# 2_PowerSupply.net
KiCad netlist of a schematic drawn in Altium Designer
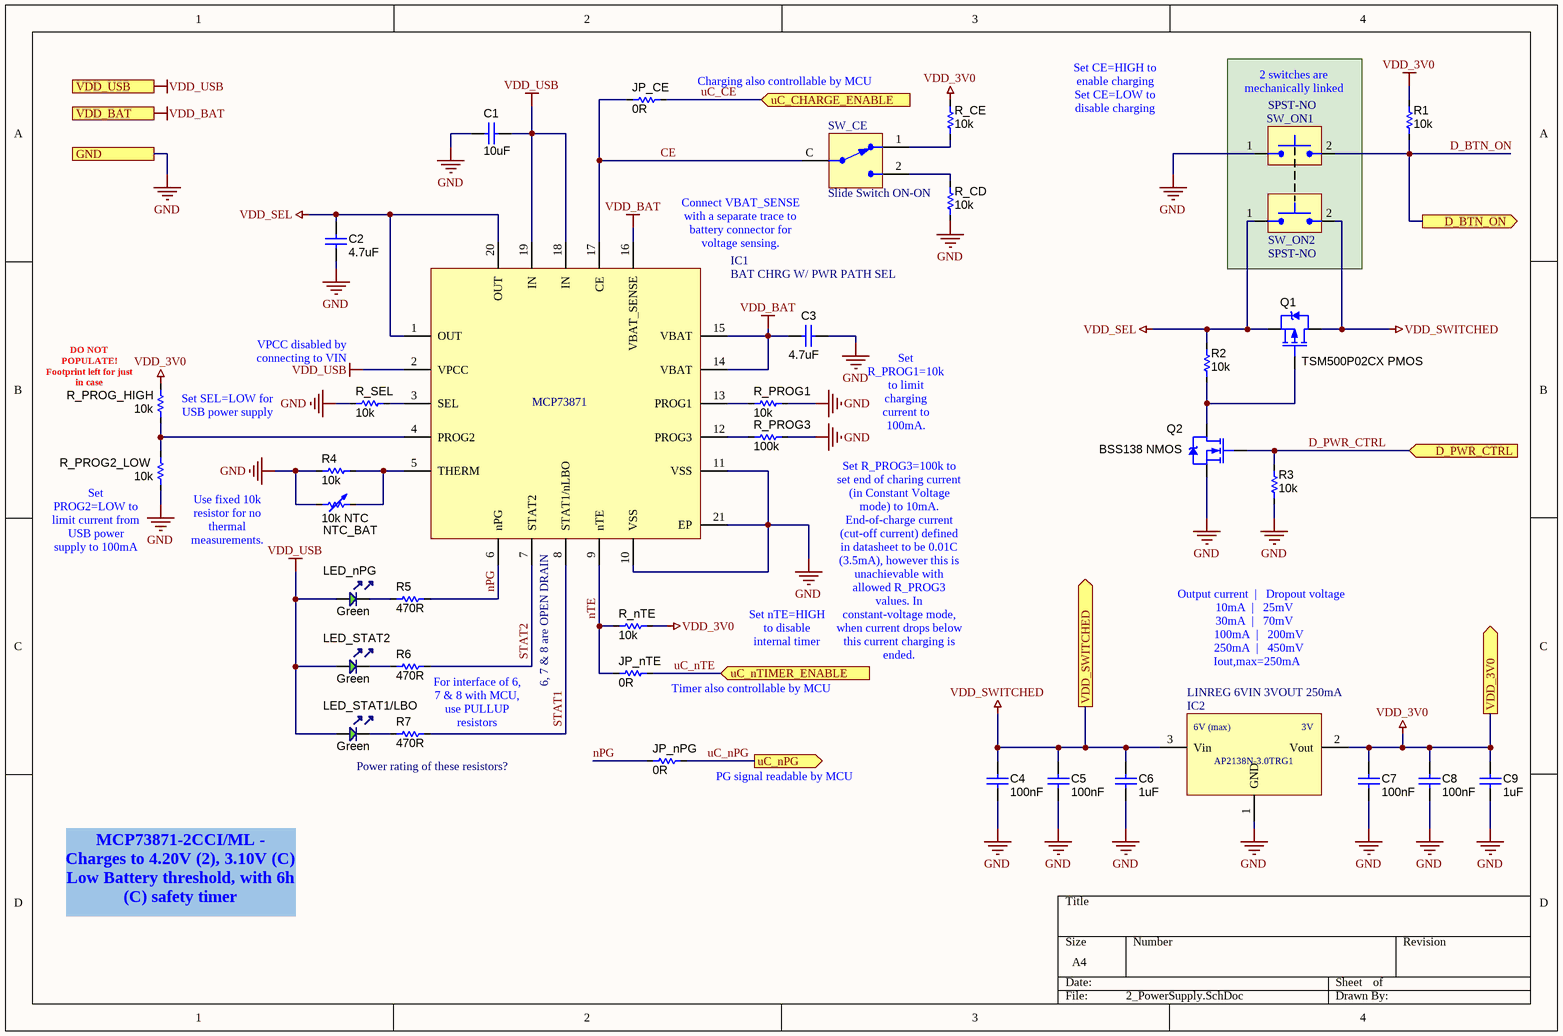
[diagram p0: 2_PowerSupply.SchDoc]

(export (version "E")
  (design (tool "Eeschema 10.0.6"))
  (components
    (comp (ref "C1")
      (value "10uF")
      (footprint "CAP_0603")
      (description "Cermacic Capacitor 0603 16V 10uF")
      (fields (field (name "MANUFACTURER") "n/a"))
      (libsource (lib "Diplomski") (part "CAP_10uF_16V_0603"))
    )
    (comp (ref "C2")
      (value "4.7uF")
      (footprint "CAP_0805")
      (description "Cermacic Capacitor 0805 25V 4.7uF")
      (fields (field (name "MANUFACTURER") "n/a"))
      (libsource (lib "Diplomski") (part "CAP_4.7uF_25V_0805"))
    )
    (comp (ref "C3")
      (value "4.7uF")
      (footprint "CAP_0805")
      (description "Cermacic Capacitor 0805 25V 4.7uF")
      (fields (field (name "MANUFACTURER") "n/a"))
      (libsource (lib "Diplomski") (part "CAP_4.7uF_25V_0805"))
    )
    (comp (ref "C4")
      (value "100nF")
      (footprint "CAP_0603")
      (description "Cermacic Capacitor 0603 50V 100nF")
      (fields (field (name "MANUFACTURER") "n/a"))
      (libsource (lib "Diplomski") (part "CAP_100nF_50V_0603"))
    )
    (comp (ref "C5")
      (value "100nF")
      (footprint "CAP_0603")
      (description "Cermacic Capacitor 0603 50V 100nF")
      (fields (field (name "MANUFACTURER") "n/a"))
      (libsource (lib "Diplomski") (part "CAP_100nF_50V_0603"))
    )
    (comp (ref "C6")
      (value "1uF")
      (footprint "CAP_0603")
      (description "Cermacic Capacitor 0603 16V 1uF")
      (fields (field (name "MANUFACTURER") "n/a"))
      (libsource (lib "Diplomski") (part "CAP_1uF_16V_0603"))
    )
    (comp (ref "C7")
      (value "100nF")
      (footprint "CAP_0603")
      (description "Cermacic Capacitor 0603 50V 100nF")
      (fields (field (name "MANUFACTURER") "n/a"))
      (libsource (lib "Diplomski") (part "CAP_100nF_50V_0603"))
    )
    (comp (ref "C8")
      (value "100nF")
      (footprint "CAP_0603")
      (description "Cermacic Capacitor 0603 50V 100nF")
      (fields (field (name "MANUFACTURER") "n/a"))
      (libsource (lib "Diplomski") (part "CAP_100nF_50V_0603"))
    )
    (comp (ref "C9")
      (value "1uF")
      (footprint "CAP_0603")
      (description "Cermacic Capacitor 0603 16V 1uF")
      (fields (field (name "MANUFACTURER") "n/a"))
      (libsource (lib "Diplomski") (part "CAP_1uF_16V_0603"))
    )
    (comp (ref "IC1")
      (value "BAT CHRG W/ PWR PATH SEL")
      (footprint "20-VFQFN EP (4mm x 4mm)")
      (fields
        (field (name "MANUFACTURER") "Microchip")
        (field (name "MANUFACTURER PART NUMBER") "MCP73871-2CCI/ML")
      )
      (libsource (lib "Diplomski") (part "IC_BATCHRG_PWRPATH_MCP73871"))
    )
    (comp (ref "IC2")
      (value "LINREG 6VIN 3VOUT 250mA")
      (footprint "SOT-23-3")
      (description "IC Linear Regulator Fixed 3V 250mA 6Vinmax SOT-23-3")
      (fields
        (field (name "MANUFACTURER") "Diodes Incorporated")
        (field (name "MANUFACTURER PART NUMBER") "AP2138N-3.0TRG1")
      )
      (libsource (lib "Diplomski") (part "IC_LINREG_6V_3V_250mA_SOT23-3"))
    )
    (comp (ref "JP_CE")
      (value "0R")
      (footprint "RES_0603")
      (description "Resistor SMD 0603 0R 0.1W 1%")
      (fields (field (name "MANUFACTURER") "n/a") (field (name "TOLERANCE") "1%"))
      (libsource (lib "Diplomski") (part "RES_0R_1%_0.1W_0603"))
    )
    (comp (ref "JP_nPG")
      (value "0R")
      (footprint "RES_0603")
      (description "Resistor SMD 0603 0R 0.1W 1%")
      (fields (field (name "MANUFACTURER") "n/a") (field (name "TOLERANCE") "1%"))
      (libsource (lib "Diplomski") (part "RES_0R_1%_0.1W_0603"))
    )
    (comp (ref "JP_nTE")
      (value "0R")
      (footprint "RES_0603")
      (description "Resistor SMD 0603 0R 0.1W 1%")
      (fields (field (name "MANUFACTURER") "n/a") (field (name "TOLERANCE") "1%"))
      (libsource (lib "Diplomski") (part "RES_0R_1%_0.1W_0603"))
    )
    (comp (ref "LED_nPG")
      (value "Green")
      (footprint "LED_0603")
      (description "LED Diode SMD Green")
      (fields (field (name "MANUFACTURER") "n/a"))
      (libsource (lib "Diplomski") (part "LED_Green_3V_20mA_0603"))
    )
    (comp (ref "LED_STAT1/LBO")
      (value "Green")
      (footprint "LED_0603")
      (description "LED Diode SMD Green")
      (fields (field (name "MANUFACTURER") "n/a"))
      (libsource (lib "Diplomski") (part "LED_Green_3V_20mA_0603"))
    )
    (comp (ref "LED_STAT2")
      (value "Green")
      (footprint "LED_0603")
      (description "LED Diode SMD Green")
      (fields (field (name "MANUFACTURER") "n/a"))
      (libsource (lib "Diplomski") (part "LED_Green_3V_20mA_0603"))
    )
    (comp (ref "NTC_BAT")
      (value "10k NTC")
      (footprint "RES VERT TH 5MM")
      (description "Thermistor NTC though-hole 10k @ 25degC 1/4W 10%")
      (fields (field (name "MANUFACTURER") "n/a") (field (name "TOLERANCE") "10%"))
      (libsource (lib "Diplomski") (part "THERM_NTC_10k_10%_0.25W_TH"))
    )
    (comp (ref "Q1")
      (value "TSM500P02CX PMOS")
      (footprint "SOT-23-3")
      (description "MOSFET P-channel SMD TSM500P02CX")
      (fields
        (field (name "MANUFACTURER") "Taiwan Semiconductor")
        (field (name "MANUFACTURER PART NUMBER") "TSM500P02CX")
      )
      (libsource (lib "Diplomski") (part "MOSFET_P_20V_4.7A_TSM500P02CX_SOT-23"))
    )
    (comp (ref "Q2")
      (value "BSS138 NMOS")
      (footprint "SOT-23-3")
      (description "MOSFET N-channel SMD BSS138 220mA 50V")
      (fields (field (name "MANUFACTURER") "ONsemi") (field (name "MANUFACTURER PART NUMBER") "BSS138"))
      (libsource (lib "Diplomski") (part "MOSFET_N_60V_220mA_BSS138_SOT-23"))
    )
    (comp (ref "R1")
      (value "10k")
      (footprint "RES_0603")
      (description "Resistor SMD 0603 10k 0.1W 1%")
      (fields (field (name "MANUFACTURER") "n/a") (field (name "TOLERANCE") "1%"))
      (libsource (lib "Diplomski") (part "RES_10k_1%_0.1W_0603"))
    )
    (comp (ref "R2")
      (value "10k")
      (footprint "RES_0603")
      (description "Resistor SMD 0603 10k 0.1W 1%")
      (fields (field (name "MANUFACTURER") "n/a") (field (name "TOLERANCE") "1%"))
      (libsource (lib "Diplomski") (part "RES_10k_1%_0.1W_0603"))
    )
    (comp (ref "R3")
      (value "10k")
      (footprint "RES_0603")
      (description "Resistor SMD 0603 10k 0.1W 1%")
      (fields (field (name "MANUFACTURER") "n/a") (field (name "TOLERANCE") "1%"))
      (libsource (lib "Diplomski") (part "RES_10k_1%_0.1W_0603"))
    )
    (comp (ref "R4")
      (value "10k")
      (footprint "RES_0603")
      (description "Resistor SMD 0603 10k 0.1W 1%")
      (fields (field (name "MANUFACTURER") "n/a") (field (name "TOLERANCE") "1%"))
      (libsource (lib "Diplomski") (part "RES_10k_1%_0.1W_0603"))
    )
    (comp (ref "R5")
      (value "470R")
      (footprint "RES_0603")
      (description "Resistor SMD 0603 0R 0.1W 1%")
      (fields (field (name "MANUFACTURER") "n/a") (field (name "TOLERANCE") "1%"))
      (libsource (lib "Diplomski") (part "RES_470R_1%_0.1W_0603"))
    )
    (comp (ref "R6")
      (value "470R")
      (footprint "RES_0603")
      (description "Resistor SMD 0603 0R 0.1W 1%")
      (fields (field (name "MANUFACTURER") "n/a") (field (name "TOLERANCE") "1%"))
      (libsource (lib "Diplomski") (part "RES_470R_1%_0.1W_0603"))
    )
    (comp (ref "R7")
      (value "470R")
      (footprint "RES_0603")
      (description "Resistor SMD 0603 0R 0.1W 1%")
      (fields (field (name "MANUFACTURER") "n/a") (field (name "TOLERANCE") "1%"))
      (libsource (lib "Diplomski") (part "RES_470R_1%_0.1W_0603"))
    )
    (comp (ref "R_CD")
      (value "10k")
      (footprint "RES_0603")
      (description "Resistor SMD 0603 10k 0.1W 1%")
      (fields (field (name "MANUFACTURER") "n/a") (field (name "TOLERANCE") "1%"))
      (libsource (lib "Diplomski") (part "RES_10k_1%_0.1W_0603"))
    )
    (comp (ref "R_CE")
      (value "10k")
      (footprint "RES_0603")
      (description "Resistor SMD 0603 10k 0.1W 1%")
      (fields (field (name "MANUFACTURER") "n/a") (field (name "TOLERANCE") "1%"))
      (libsource (lib "Diplomski") (part "RES_10k_1%_0.1W_0603"))
    )
    (comp (ref "R_nTE")
      (value "10k")
      (footprint "RES_0603")
      (description "Resistor SMD 0603 10k 0.1W 1%")
      (fields (field (name "MANUFACTURER") "n/a") (field (name "TOLERANCE") "1%"))
      (libsource (lib "Diplomski") (part "RES_10k_1%_0.1W_0603"))
    )
    (comp (ref "R_PROG1")
      (value "10k")
      (footprint "RES_0603")
      (description "Resistor SMD 0603 10k 0.1W 1%")
      (fields (field (name "MANUFACTURER") "n/a") (field (name "TOLERANCE") "1%"))
      (libsource (lib "Diplomski") (part "RES_10k_1%_0.1W_0603"))
    )
    (comp (ref "R_PROG2_LOW")
      (value "10k")
      (footprint "RES_0603")
      (description "Resistor SMD 0603 10k 0.1W 1%")
      (fields (field (name "MANUFACTURER") "n/a") (field (name "TOLERANCE") "1%"))
      (libsource (lib "Diplomski") (part "RES_10k_1%_0.1W_0603"))
    )
    (comp (ref "R_PROG3")
      (value "100k")
      (footprint "RES_0603")
      (description "Resistor SMD 0603 100k 0.1W 1%")
      (fields (field (name "MANUFACTURER") "n/a") (field (name "TOLERANCE") "1%"))
      (libsource (lib "Diplomski") (part "RES_100k_1%_0.1W_0603"))
    )
    (comp (ref "R_PROG_HIGH")
      (value "10k")
      (footprint "RES_0603")
      (description "Resistor SMD 0603 10k 0.1W 1%")
      (fields (field (name "MANUFACTURER") "n/a") (field (name "TOLERANCE") "1%"))
      (libsource (lib "Diplomski") (part "RES_10k_1%_0.1W_0603"))
    )
    (comp (ref "R_SEL")
      (value "10k")
      (footprint "RES_0603")
      (description "Resistor SMD 0603 10k 0.1W 1%")
      (fields (field (name "MANUFACTURER") "n/a") (field (name "TOLERANCE") "1%"))
      (libsource (lib "Diplomski") (part "RES_10k_1%_0.1W_0603"))
    )
    (comp (ref "SW_CE")
      (value "Slide Switch ON-ON")
      (footprint "SWITCH SPDT 2.54MM R/A")
      (description "Slide switch 2.54mm pitch Single Pole Double Throw (ON-ON) ESP201 Right Angle")
      (fields (field (name "MANUFACTURER") "ECE") (field (name "MANUFACTURER PART NUMBER") "ESP201"))
      (libsource (lib "Diplomski") (part "SWITCH_SLIDE_SPDT_ESP201_R/A_2.54mm"))
    )
    (comp (ref "SW_ON1")
      (value "SPST-NO")
      (footprint "SWITCH_TACTILE_SMD_6X3.5mm_2pin")
      (description "SMD Tactile switch 2 pin 6x3.5mm SPST-NO 5mm height")
      (fields (field (name "MANUFACTURER") "Diptronics") (field (name "MANUFACTURER PART NUMBER") "DTSM-32N"))
      (libsource (lib "Diplomski") (part "SWITCH_SMD_6X3.5mm_2pin"))
    )
    (comp (ref "SW_ON2")
      (value "SPST-NO")
      (footprint "SWITCH_TACTILE_SMD_6X3.5mm_2pin")
      (description "SMD Tactile switch 2 pin 6x3.5mm SPST-NO 5mm height")
      (fields (field (name "MANUFACTURER") "Diptronics") (field (name "MANUFACTURER PART NUMBER") "DTSM-32N"))
      (libsource (lib "Diplomski") (part "SWITCH_SMD_6X3.5mm_2pin"))
    )
  )
  (nets
    (net (code "1") (name "/CE") (class "Default")
      (node (ref "IC1") (pin "17") (pinfunction "CE_17") (pintype "passive"))
      (node (ref "JP_CE") (pin "1") (pinfunction "1_1") (pintype "passive"))
      (node (ref "SW_CE") (pin "C") (pinfunction "C_C") (pintype "passive"))
    )
    (net (code "2") (name "/D_BTN_ON") (class "Default")
      (node (ref "R1") (pin "1") (pinfunction "1_1") (pintype "passive"))
      (node (ref "SW_ON1") (pin "2") (pinfunction "2_2") (pintype "passive"))
    )
    (net (code "3") (name "/D_PWR_CTRL") (class "Default")
      (node (ref "Q2") (pin "1") (pinfunction "G_1") (pintype "passive"))
      (node (ref "R3") (pin "2") (pinfunction "2_2") (pintype "passive"))
    )
    (net (code "4") (name "/STAT1") (class "Default")
      (node (ref "IC1") (pin "8") (pinfunction "STAT1/nLBO_8") (pintype "passive"))
      (node (ref "R7") (pin "2") (pinfunction "2_2") (pintype "passive"))
    )
    (net (code "5") (name "/STAT2") (class "Default")
      (node (ref "IC1") (pin "7") (pinfunction "STAT2_7") (pintype "passive"))
      (node (ref "R6") (pin "2") (pinfunction "2_2") (pintype "passive"))
    )
    (net (code "6") (name "/nPG") (class "Default")
      (node (ref "IC1") (pin "6") (pinfunction "nPG_6") (pintype "passive"))
      (node (ref "JP_nPG") (pin "2") (pinfunction "2_2") (pintype "passive"))
      (node (ref "R5") (pin "2") (pinfunction "2_2") (pintype "passive"))
    )
    (net (code "7") (name "/nTE") (class "Default")
      (node (ref "IC1") (pin "9") (pinfunction "nTE_9") (pintype "passive"))
      (node (ref "JP_nTE") (pin "2") (pinfunction "2_2") (pintype "passive"))
      (node (ref "R_nTE") (pin "1") (pinfunction "1_1") (pintype "passive"))
    )
    (net (code "8") (name "/uC_CE") (class "Default")
      (node (ref "JP_CE") (pin "2") (pinfunction "2_2") (pintype "passive"))
    )
    (net (code "9") (name "/uC_nPG") (class "Default")
      (node (ref "JP_nPG") (pin "1") (pinfunction "1_1") (pintype "passive"))
    )
    (net (code "10") (name "/uC_nTE") (class "Default")
      (node (ref "JP_nTE") (pin "1") (pinfunction "1_1") (pintype "passive"))
    )
    (net (code "11") (name "GND") (class "Default")
      (node (ref "C1") (pin "2") (pinfunction "2_2") (pintype "passive"))
      (node (ref "C2") (pin "2") (pinfunction "2_2") (pintype "passive"))
      (node (ref "C3") (pin "2") (pinfunction "2_2") (pintype "passive"))
      (node (ref "C4") (pin "2") (pinfunction "2_2") (pintype "passive"))
      (node (ref "C5") (pin "2") (pinfunction "2_2") (pintype "passive"))
      (node (ref "C6") (pin "2") (pinfunction "2_2") (pintype "passive"))
      (node (ref "C7") (pin "2") (pinfunction "2_2") (pintype "passive"))
      (node (ref "C8") (pin "2") (pinfunction "2_2") (pintype "passive"))
      (node (ref "C9") (pin "2") (pinfunction "2_2") (pintype "passive"))
      (node (ref "IC1") (pin "10") (pinfunction "VSS_10") (pintype "passive"))
      (node (ref "IC1") (pin "11") (pinfunction "VSS_11") (pintype "passive"))
      (node (ref "IC1") (pin "21") (pinfunction "EP_21") (pintype "passive"))
      (node (ref "IC2") (pin "1") (pinfunction "GND_1") (pintype "passive"))
      (node (ref "NTC_BAT") (pin "1") (pinfunction "1_1") (pintype "passive"))
      (node (ref "Q2") (pin "2") (pinfunction "S_2") (pintype "passive"))
      (node (ref "R3") (pin "1") (pinfunction "1_1") (pintype "passive"))
      (node (ref "R4") (pin "1") (pinfunction "1_1") (pintype "passive"))
      (node (ref "R_CD") (pin "1") (pinfunction "1_1") (pintype "passive"))
      (node (ref "R_PROG1") (pin "1") (pinfunction "1_1") (pintype "passive"))
      (node (ref "R_PROG2_LOW") (pin "1") (pinfunction "1_1") (pintype "passive"))
      (node (ref "R_PROG3") (pin "2") (pinfunction "2_2") (pintype "passive"))
      (node (ref "R_SEL") (pin "1") (pinfunction "1_1") (pintype "passive"))
      (node (ref "SW_ON1") (pin "1") (pinfunction "1_1") (pintype "passive"))
    )
    (net (code "12") (name "Net-(IC1-PROG1)") (class "Default")
      (node (ref "IC1") (pin "13") (pinfunction "PROG1_13") (pintype "passive"))
      (node (ref "R_PROG1") (pin "2") (pinfunction "2_2") (pintype "passive"))
    )
    (net (code "13") (name "Net-(IC1-PROG2)") (class "Default")
      (node (ref "IC1") (pin "4") (pinfunction "PROG2_4") (pintype "passive"))
      (node (ref "R_PROG2_LOW") (pin "2") (pinfunction "2_2") (pintype "passive"))
      (node (ref "R_PROG_HIGH") (pin "1") (pinfunction "1_1") (pintype "passive"))
    )
    (net (code "14") (name "Net-(IC1-PROG3)") (class "Default")
      (node (ref "IC1") (pin "12") (pinfunction "PROG3_12") (pintype "passive"))
      (node (ref "R_PROG3") (pin "1") (pinfunction "1_1") (pintype "passive"))
    )
    (net (code "15") (name "Net-(IC1-SEL)") (class "Default")
      (node (ref "IC1") (pin "3") (pinfunction "SEL_3") (pintype "passive"))
      (node (ref "R_SEL") (pin "2") (pinfunction "2_2") (pintype "passive"))
    )
    (net (code "16") (name "Net-(IC1-THERM)") (class "Default")
      (node (ref "IC1") (pin "5") (pinfunction "THERM_5") (pintype "passive"))
      (node (ref "NTC_BAT") (pin "2") (pinfunction "2_2") (pintype "passive"))
      (node (ref "R4") (pin "2") (pinfunction "2_2") (pintype "passive"))
    )
    (net (code "17") (name "Net-(LED_STAT1/LBO-PadK)") (class "Default")
      (node (ref "LED_STAT1/LBO") (pin "K") (pinfunction "K_K") (pintype "passive"))
      (node (ref "R7") (pin "1") (pinfunction "1_1") (pintype "passive"))
    )
    (net (code "18") (name "Net-(LED_STAT2-PadK)") (class "Default")
      (node (ref "LED_STAT2") (pin "K") (pinfunction "K_K") (pintype "passive"))
      (node (ref "R6") (pin "1") (pinfunction "1_1") (pintype "passive"))
    )
    (net (code "19") (name "Net-(LED_nPG-PadK)") (class "Default")
      (node (ref "LED_nPG") (pin "K") (pinfunction "K_K") (pintype "passive"))
      (node (ref "R5") (pin "1") (pinfunction "1_1") (pintype "passive"))
    )
    (net (code "20") (name "Net-(Q1-G)") (class "Default")
      (node (ref "Q1") (pin "1") (pinfunction "G_1") (pintype "passive"))
      (node (ref "Q2") (pin "3") (pinfunction "D_3") (pintype "passive"))
      (node (ref "R2") (pin "1") (pinfunction "1_1") (pintype "passive"))
    )
    (net (code "21") (name "Net-(R_CD-Pad2)") (class "Default")
      (node (ref "R_CD") (pin "2") (pinfunction "2_2") (pintype "passive"))
      (node (ref "SW_CE") (pin "2") (pinfunction "2_2") (pintype "passive"))
    )
    (net (code "22") (name "Net-(R_CE-Pad2)") (class "Default")
      (node (ref "R_CE") (pin "2") (pinfunction "2_2") (pintype "passive"))
      (node (ref "SW_CE") (pin "1") (pinfunction "1_1") (pintype "passive"))
    )
    (net (code "23") (name "VDD_3V0") (class "Default")
      (node (ref "C7") (pin "1") (pinfunction "1_1") (pintype "passive"))
      (node (ref "C8") (pin "1") (pinfunction "1_1") (pintype "passive"))
      (node (ref "C9") (pin "1") (pinfunction "1_1") (pintype "passive"))
      (node (ref "IC2") (pin "2") (pinfunction "Vout_2") (pintype "passive"))
      (node (ref "R1") (pin "2") (pinfunction "2_2") (pintype "passive"))
      (node (ref "R_CE") (pin "1") (pinfunction "1_1") (pintype "passive"))
      (node (ref "R_PROG_HIGH") (pin "2") (pinfunction "2_2") (pintype "passive"))
      (node (ref "R_nTE") (pin "2") (pinfunction "2_2") (pintype "passive"))
    )
    (net (code "24") (name "VDD_BAT") (class "Default")
      (node (ref "C3") (pin "1") (pinfunction "1_1") (pintype "passive"))
      (node (ref "IC1") (pin "14") (pinfunction "VBAT_14") (pintype "passive"))
      (node (ref "IC1") (pin "15") (pinfunction "VBAT_15") (pintype "passive"))
      (node (ref "IC1") (pin "16") (pinfunction "VBAT_SENSE_16") (pintype "passive"))
    )
    (net (code "25") (name "VDD_SEL") (class "Default")
      (node (ref "C2") (pin "1") (pinfunction "1_1") (pintype "passive"))
      (node (ref "IC1") (pin "1") (pinfunction "OUT_1") (pintype "passive"))
      (node (ref "IC1") (pin "20") (pinfunction "OUT_20") (pintype "passive"))
      (node (ref "Q1") (pin "2") (pinfunction "S_2") (pintype "passive"))
      (node (ref "R2") (pin "2") (pinfunction "2_2") (pintype "passive"))
      (node (ref "SW_ON2") (pin "1") (pinfunction "1_1") (pintype "passive"))
    )
    (net (code "26") (name "VDD_SWITCHED") (class "Default")
      (node (ref "C4") (pin "1") (pinfunction "1_1") (pintype "passive"))
      (node (ref "C5") (pin "1") (pinfunction "1_1") (pintype "passive"))
      (node (ref "C6") (pin "1") (pinfunction "1_1") (pintype "passive"))
      (node (ref "IC2") (pin "3") (pinfunction "Vin_3") (pintype "passive"))
      (node (ref "Q1") (pin "3") (pinfunction "D_3") (pintype "passive"))
      (node (ref "SW_ON2") (pin "2") (pinfunction "2_2") (pintype "passive"))
    )
    (net (code "27") (name "VDD_USB") (class "Default")
      (node (ref "C1") (pin "1") (pinfunction "1_1") (pintype "passive"))
      (node (ref "IC1") (pin "18") (pinfunction "IN_18") (pintype "passive"))
      (node (ref "IC1") (pin "19") (pinfunction "IN_19") (pintype "passive"))
      (node (ref "IC1") (pin "2") (pinfunction "VPCC_2") (pintype "passive"))
      (node (ref "LED_STAT1/LBO") (pin "A") (pinfunction "A_A") (pintype "passive"))
      (node (ref "LED_STAT2") (pin "A") (pinfunction "A_A") (pintype "passive"))
      (node (ref "LED_nPG") (pin "A") (pinfunction "A_A") (pintype "passive"))
    )
  )
)
